# ASBB_VIN.net
KiCad netlist of a schematic drawn in Altium Designer
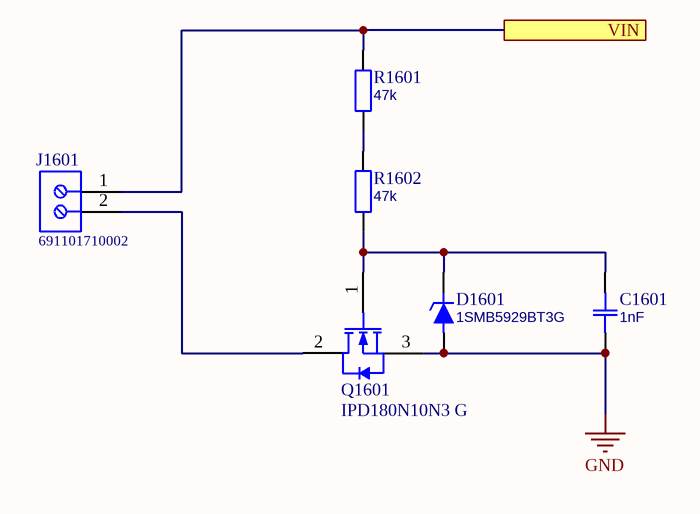
[diagram p0: ASBB_VIN.SchDoc]

(export (version "E")
  (design (tool "Eeschema 10.0.6"))
  (components
    (comp (ref "C1601")
      (value "1nF")
      (footprint "0603")
      (description "Capacitor")
      (fields (field (name "PARTNUMBER") "?"))
      (libsource (lib "FZI") (part "Capacitor"))
    )
    (comp (ref "D1601")
      (value "1SMB5929BT3G")
      (footprint "SMB")
      (description "Zener Diode / Varistor unipolar")
      (fields (field (name "PARTNUMBER") "?"))
      (libsource (lib "FZI") (part "Diode Zener"))
    )
    (comp (ref "J1601")
      (value "691101710002")
      (footprint "691101710002")
      (description "Series 101 - 5.00 mm Horizontal Entry Modular with Pressure Clamp WR-TBL, 2 pin")
      (fields (field (name "PUBLISHER") "Wurth Elektronik"))
      (libsource (lib "Altium_WR-TBL_Wire_Protector_System (rev18a)") (part "691101710002"))
    )
    (comp (ref "Q1601")
      (value "IPD180N10N3 G")
      (footprint "INF-PG-TO252-3-11_A_N")
      (fields (field (name "MANUFACTURER") "Infineon"))
      (libsource (lib "Infineon_Power_MOSFET") (part "IPD180N10N3 G"))
    )
    (comp (ref "R1601")
      (value "47k")
      (footprint "0603")
      (description "Resistor")
      (fields (field (name "PARTNUMBER") "?"))
      (libsource (lib "FZI") (part "Resistor"))
    )
    (comp (ref "R1602")
      (value "47k")
      (footprint "0603")
      (description "Resistor")
      (fields (field (name "PARTNUMBER") "?"))
      (libsource (lib "FZI") (part "Resistor"))
    )
  )
  (nets
    (net (code "1") (name "/VIN") (class "Default")
      (node (ref "J1601") (pin "1") (pinfunction "1_1") (pintype "passive"))
      (node (ref "R1601") (pin "2") (pinfunction "2_2") (pintype "passive"))
    )
    (net (code "2") (name "GND") (class "Default")
      (node (ref "C1601") (pin "2") (pinfunction "2_2") (pintype "passive"))
      (node (ref "D1601") (pin "2") (pinfunction "A_2") (pintype "passive"))
      (node (ref "Q1601") (pin "3") (pinfunction "SOURCE_3") (pintype "passive"))
    )
    (net (code "3") (name "Net-(D1601-C)") (class "Default")
      (node (ref "C1601") (pin "1") (pinfunction "1_1") (pintype "passive"))
      (node (ref "D1601") (pin "1") (pinfunction "C_1") (pintype "passive"))
      (node (ref "Q1601") (pin "1") (pinfunction "GATE_1") (pintype "passive"))
      (node (ref "R1602") (pin "1") (pinfunction "1_1") (pintype "passive"))
    )
    (net (code "4") (name "Net-(Q1601-DRAIN)") (class "Default")
      (node (ref "J1601") (pin "2") (pinfunction "2_2") (pintype "passive"))
      (node (ref "Q1601") (pin "2") (pinfunction "DRAIN_2") (pintype "passive"))
    )
    (net (code "5") (name "Net-(R1601-Pad1)") (class "Default")
      (node (ref "R1601") (pin "1") (pinfunction "1_1") (pintype "passive"))
      (node (ref "R1602") (pin "2") (pinfunction "2_2") (pintype "passive"))
    )
  )
)
